# ngff-breakout.net
KiCad netlist of a schematic drawn in EAGLE
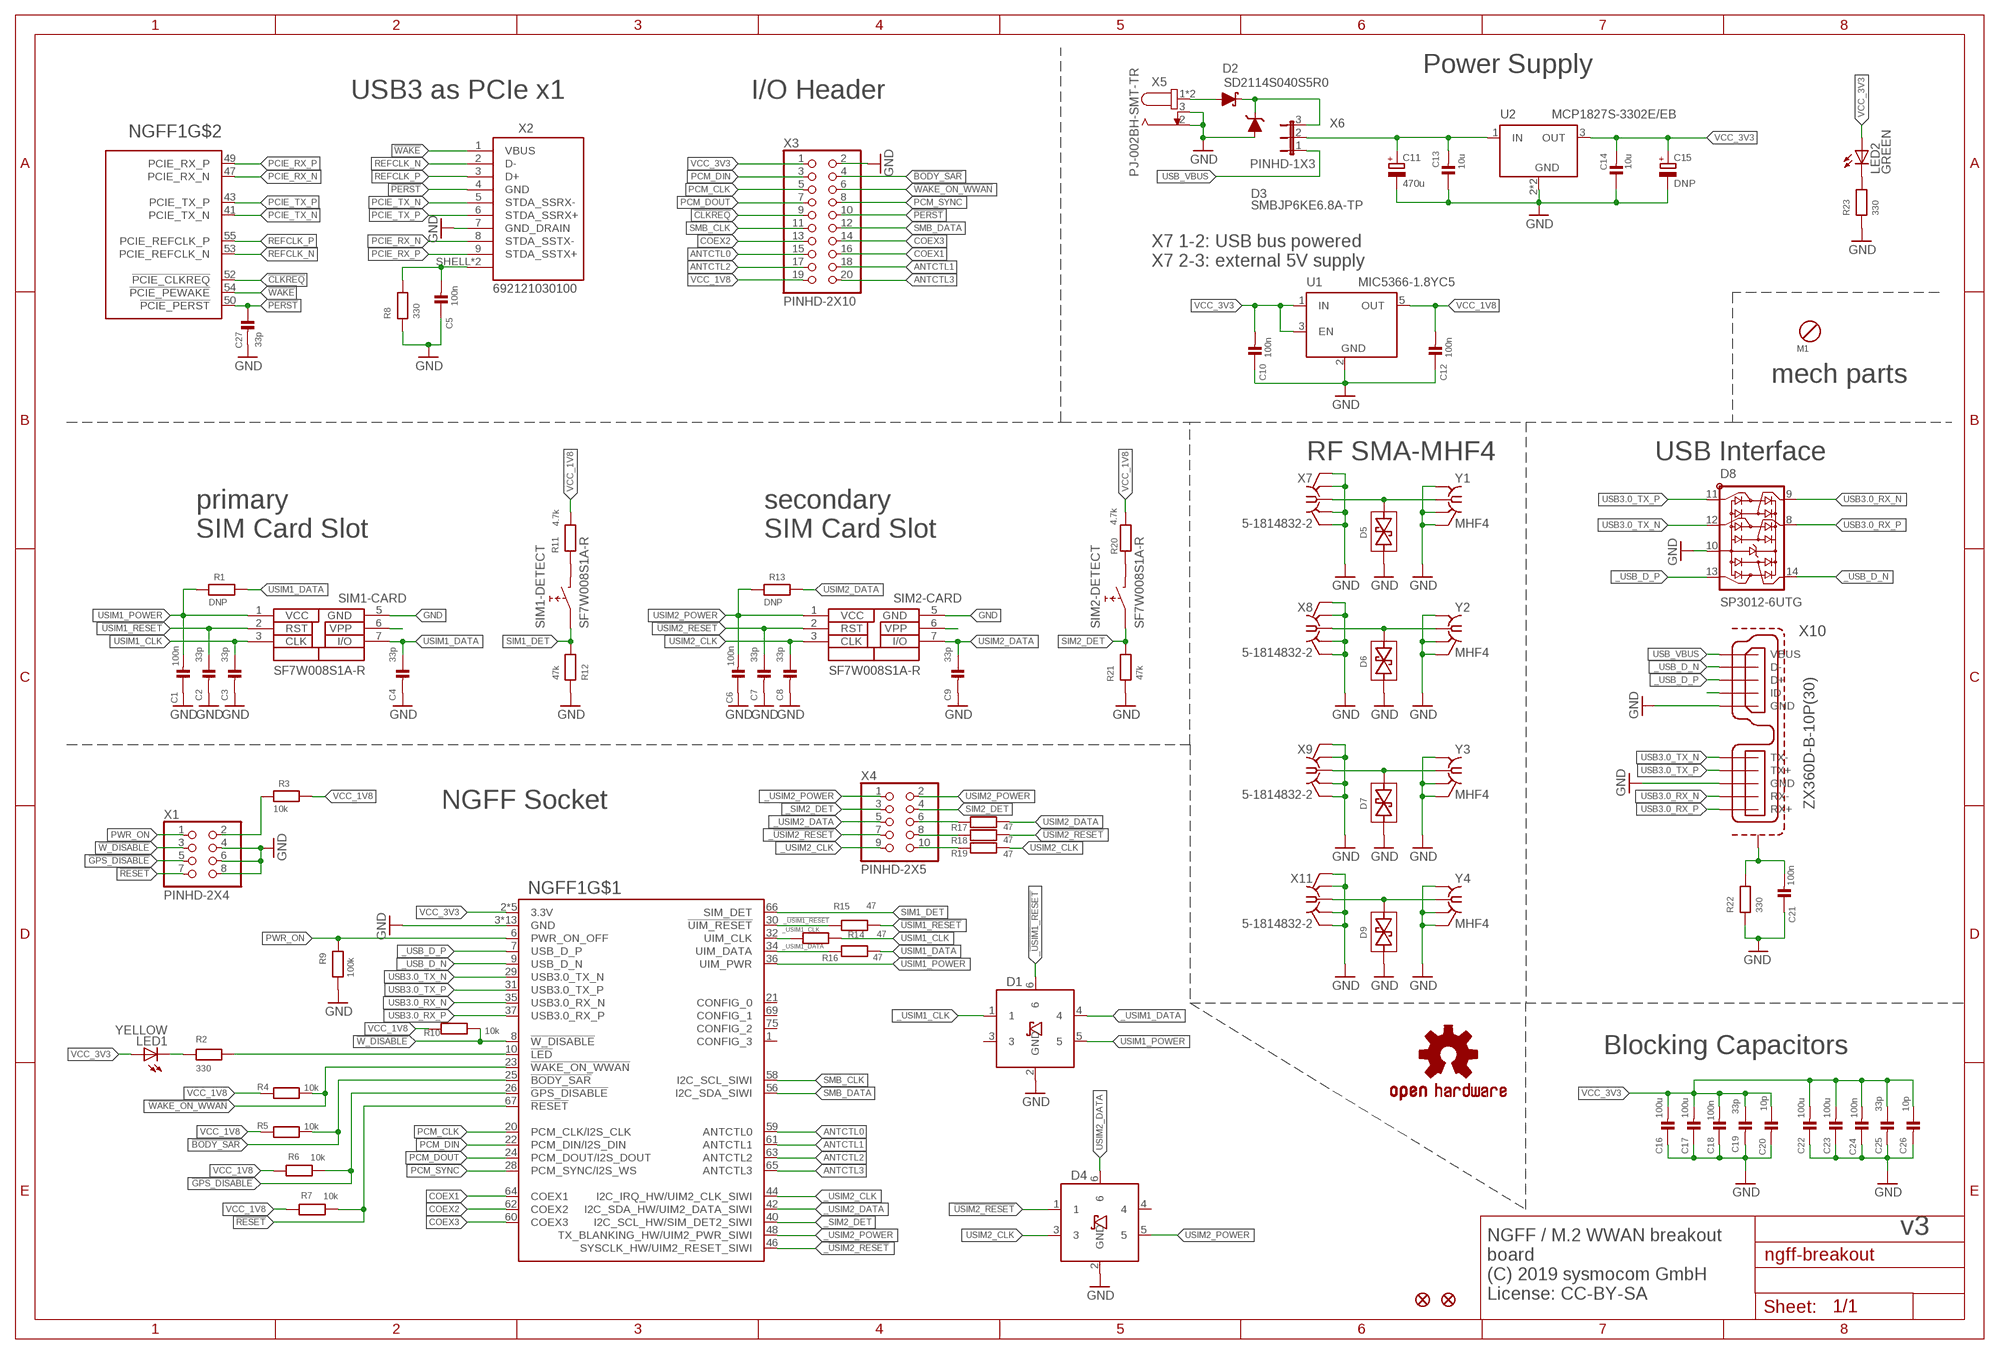
[diagram p0: schematic, sheet 1]

(export (version "E")
  (design (tool "Eeschema 10.0.6"))
  (components
    (comp (ref "C1")
      (value "100n")
      (footprint "eagle-import:_0603")
      (description "CAP CER 0.1UF 16V 10% X7R 0603")
      (fields
        (field (name "MANUFACTURER") "Samsung Electro-Mechanics America, Inc")
        (field (name "MANUFACTURERPARTNUMBER") "CL10B104KO8NNNC")
      )
      (libsource (lib "eagle-import") (part "CAP_CERAMIC_0603"))
    )
    (comp (ref "C2")
      (value "33p")
      (footprint "eagle-import:_0402")
      (description "CAP CER 33PF 50V NP0 0402")
      (fields
        (field (name "MANUFACTURER") "Samsung Electro-Mechanics America, Inc.")
        (field (name "MANUFACTURERPARTNUMBER") "CL05C330JB5NNNC")
      )
      (libsource (lib "eagle-import") (part "CAP_CERAMIC_0402"))
    )
    (comp (ref "C3")
      (value "33p")
      (footprint "eagle-import:_0402")
      (description "CAP CER 33PF 50V NP0 0402")
      (fields
        (field (name "MANUFACTURER") "Samsung Electro-Mechanics America, Inc.")
        (field (name "MANUFACTURERPARTNUMBER") "CL05C330JB5NNNC")
      )
      (libsource (lib "eagle-import") (part "CAP_CERAMIC_0402"))
    )
    (comp (ref "C4")
      (value "33p")
      (footprint "eagle-import:_0402")
      (description "CAP CER 33PF 50V NP0 0402")
      (fields
        (field (name "MANUFACTURER") "Samsung Electro-Mechanics America, Inc.")
        (field (name "MANUFACTURERPARTNUMBER") "CL05C330JB5NNNC")
      )
      (libsource (lib "eagle-import") (part "CAP_CERAMIC_0402"))
    )
    (comp (ref "C5")
      (value "100n")
      (footprint "eagle-import:_0603")
      (description "CAP CER 0.1UF 16V 10% X7R 0603")
      (fields
        (field (name "MANUFACTURER") "Samsung Electro-Mechanics America, Inc")
        (field (name "MANUFACTURERPARTNUMBER") "CL10B104KO8NNNC")
      )
      (libsource (lib "eagle-import") (part "CAP_CERAMIC_0603"))
    )
    (comp (ref "C6")
      (value "100n")
      (footprint "eagle-import:_0603")
      (description "CAP CER 0.1UF 16V 10% X7R 0603")
      (fields
        (field (name "MANUFACTURER") "Samsung Electro-Mechanics America, Inc")
        (field (name "MANUFACTURERPARTNUMBER") "CL10B104KO8NNNC")
      )
      (libsource (lib "eagle-import") (part "CAP_CERAMIC_0603"))
    )
    (comp (ref "C7")
      (value "33p")
      (footprint "eagle-import:_0402")
      (description "CAP CER 33PF 50V NP0 0402")
      (fields
        (field (name "MANUFACTURER") "Samsung Electro-Mechanics America, Inc.")
        (field (name "MANUFACTURERPARTNUMBER") "CL05C330JB5NNNC")
      )
      (libsource (lib "eagle-import") (part "CAP_CERAMIC_0402"))
    )
    (comp (ref "C8")
      (value "33p")
      (footprint "eagle-import:_0402")
      (description "CAP CER 33PF 50V NP0 0402")
      (fields
        (field (name "MANUFACTURER") "Samsung Electro-Mechanics America, Inc.")
        (field (name "MANUFACTURERPARTNUMBER") "CL05C330JB5NNNC")
      )
      (libsource (lib "eagle-import") (part "CAP_CERAMIC_0402"))
    )
    (comp (ref "C9")
      (value "33p")
      (footprint "eagle-import:_0402")
      (description "CAP CER 33PF 50V NP0 0402")
      (fields
        (field (name "MANUFACTURER") "Samsung Electro-Mechanics America, Inc.")
        (field (name "MANUFACTURERPARTNUMBER") "CL05C330JB5NNNC")
      )
      (libsource (lib "eagle-import") (part "CAP_CERAMIC_0402"))
    )
    (comp (ref "C10")
      (value "100n")
      (footprint "eagle-import:_0603")
      (description "CAP CER 0.1UF 16V 10% X7R 0603")
      (fields
        (field (name "MANUFACTURER") "Samsung Electro-Mechanics America, Inc")
        (field (name "MANUFACTURERPARTNUMBER") "CL10B104KO8NNNC")
      )
      (libsource (lib "eagle-import") (part "CAP_CERAMIC_0603"))
    )
    (comp (ref "C11")
      (value "470u")
      (footprint "eagle-import:UD-8X10_NICHICON")
      (description "CAP ALUM 470UF 20%% 6.3V SMD")
      (fields
        (field (name "MANUFACTURER") "Nichicon")
        (field (name "MANUFACTURERPARTNUMBER") "UUR0J471MNL1GS")
      )
      (libsource (lib "eagle-import") (part "CPOL-EUUD-8X10"))
    )
    (comp (ref "C12")
      (value "100n")
      (footprint "eagle-import:_0603")
      (description "CAP CER 0.1UF 16V 10% X7R 0603")
      (fields
        (field (name "MANUFACTURER") "Samsung Electro-Mechanics America, Inc")
        (field (name "MANUFACTURERPARTNUMBER") "CL10B104KO8NNNC")
      )
      (libsource (lib "eagle-import") (part "CAP_CERAMIC_0603"))
    )
    (comp (ref "C13")
      (value "10u")
      (footprint "eagle-import:_0805")
      (description "CAP CER 10UF 16V X5R 0805")
      (fields
        (field (name "MANUFACTURER") "Samsung Electro-Mechanics")
        (field (name "MANUFACTURERPARTNUMBER") "CL21A106KOQNNNG")
      )
      (libsource (lib "eagle-import") (part "CAP_CERAMIC_0805"))
    )
    (comp (ref "C14")
      (value "10u")
      (footprint "eagle-import:_0805")
      (description "CAP CER 10UF 16V X5R 0805")
      (fields
        (field (name "MANUFACTURER") "Samsung Electro-Mechanics")
        (field (name "MANUFACTURERPARTNUMBER") "CL21A106KOQNNNG")
      )
      (libsource (lib "eagle-import") (part "CAP_CERAMIC_0805"))
    )
    (comp (ref "C15")
      (value "DNP")
      (footprint "eagle-import:SMC_E")
      (description "NO DESCRIPTION")
      (fields
        (field (name "MANUFACTURER") "UNKNOWN MANUFACTURER")
        (field (name "MANUFACTURERPARTNUMBER") "UNKNOWN MANUFACTURER PART NUMBER")
      )
      (libsource (lib "eagle-import") (part "CPOL-EUSMCE"))
    )
    (comp (ref "C16")
      (value "100u")
      (footprint "eagle-import:1206")
      (description "CAP CER 100UF 6.3V X5R 1206")
      (fields
        (field (name "MANUFACTURER") "Murata Electronics North America")
        (field (name "MANUFACTURERPARTNUMBER") "GRM31CR60J107ME39K")
      )
      (libsource (lib "eagle-import") (part "CAP_CERAMIC1206"))
    )
    (comp (ref "C17")
      (value "100u")
      (footprint "eagle-import:1206")
      (description "CAP CER 100UF 6.3V X5R 1206")
      (fields
        (field (name "MANUFACTURER") "Murata Electronics North America")
        (field (name "MANUFACTURERPARTNUMBER") "GRM31CR60J107ME39K")
      )
      (libsource (lib "eagle-import") (part "CAP_CERAMIC1206"))
    )
    (comp (ref "C18")
      (value "100n")
      (footprint "eagle-import:_0603")
      (description "CAP CER 0.1UF 16V 10% X7R 0603")
      (fields
        (field (name "MANUFACTURER") "Samsung Electro-Mechanics America, Inc")
        (field (name "MANUFACTURERPARTNUMBER") "CL10B104KO8NNNC")
      )
      (libsource (lib "eagle-import") (part "CAP_CERAMIC_0603"))
    )
    (comp (ref "C19")
      (value "33p")
      (footprint "eagle-import:_0402")
      (description "CAP CER 33PF 50V NP0 0402")
      (fields
        (field (name "MANUFACTURER") "Samsung Electro-Mechanics America, Inc.")
        (field (name "MANUFACTURERPARTNUMBER") "CL05C330JB5NNNC")
      )
      (libsource (lib "eagle-import") (part "CAP_CERAMIC_0402"))
    )
    (comp (ref "C20")
      (value "10p")
      (footprint "eagle-import:_0603")
      (description "CAP CER 10PF 50V NP0 0603")
      (fields
        (field (name "MANUFACTURER") "Kemet")
        (field (name "MANUFACTURERPARTNUMBER") "C0603C100J5GACTU")
      )
      (libsource (lib "eagle-import") (part "CAP_CERAMIC_0603"))
    )
    (comp (ref "C21")
      (value "100n")
      (footprint "eagle-import:_0603")
      (description "CAP CER 0.1UF 16V 10% X7R 0603")
      (fields
        (field (name "MANUFACTURER") "Samsung Electro-Mechanics America, Inc")
        (field (name "MANUFACTURERPARTNUMBER") "CL10B104KO8NNNC")
      )
      (libsource (lib "eagle-import") (part "CAP_CERAMIC_0603"))
    )
    (comp (ref "C22")
      (value "100u")
      (footprint "eagle-import:1206")
      (description "CAP CER 100UF 6.3V X5R 1206")
      (fields
        (field (name "MANUFACTURER") "Murata Electronics North America")
        (field (name "MANUFACTURERPARTNUMBER") "GRM31CR60J107ME39K")
      )
      (libsource (lib "eagle-import") (part "CAP_CERAMIC1206"))
    )
    (comp (ref "C23")
      (value "100u")
      (footprint "eagle-import:1206")
      (description "CAP CER 100UF 6.3V X5R 1206")
      (fields
        (field (name "MANUFACTURER") "Murata Electronics North America")
        (field (name "MANUFACTURERPARTNUMBER") "GRM31CR60J107ME39K")
      )
      (libsource (lib "eagle-import") (part "CAP_CERAMIC1206"))
    )
    (comp (ref "C24")
      (value "100n")
      (footprint "eagle-import:_0603")
      (description "CAP CER 0.1UF 16V 10% X7R 0603")
      (fields
        (field (name "MANUFACTURER") "Samsung Electro-Mechanics America, Inc")
        (field (name "MANUFACTURERPARTNUMBER") "CL10B104KO8NNNC")
      )
      (libsource (lib "eagle-import") (part "CAP_CERAMIC_0603"))
    )
    (comp (ref "C25")
      (value "33p")
      (footprint "eagle-import:_0402")
      (description "CAP CER 33PF 50V NP0 0402")
      (fields
        (field (name "MANUFACTURER") "Samsung Electro-Mechanics America, Inc.")
        (field (name "MANUFACTURERPARTNUMBER") "CL05C330JB5NNNC")
      )
      (libsource (lib "eagle-import") (part "CAP_CERAMIC_0402"))
    )
    (comp (ref "C26")
      (value "10p")
      (footprint "eagle-import:_0603")
      (description "CAP CER 10PF 50V NP0 0603")
      (fields
        (field (name "MANUFACTURER") "Kemet")
        (field (name "MANUFACTURERPARTNUMBER") "C0603C100J5GACTU")
      )
      (libsource (lib "eagle-import") (part "CAP_CERAMIC_0603"))
    )
    (comp (ref "C27")
      (value "33p")
      (footprint "eagle-import:_0402")
      (description "CAP CER 33PF 50V NP0 0402")
      (fields
        (field (name "MANUFACTURER") "Samsung Electro-Mechanics America, Inc.")
        (field (name "MANUFACTURERPARTNUMBER") "CL05C330JB5NNNC")
      )
      (libsource (lib "eagle-import") (part "CAP_CERAMIC_0402"))
    )
    (comp (ref "D1")
      (value "PESD5V0UBV")
      (footprint "eagle-import:SOT666")
      (description "TVS DIODE 5V SOT666")
      (fields
        (field (name "MANUFACTURER") "Nexperia USA Inc.")
        (field (name "MANUFACTURERPARTNUMBER") "PESD5V0U5BV,115")
      )
      (libsource (lib "eagle-import") (part "PESD5V0UBV"))
    )
    (comp (ref "D2")
      (value "SD2114S040S5R0")
      (footprint "eagle-import:SMBDIODE")
      (description "DIODE SCHOTTKY 40V 5A SMB")
      (fields
        (field (name "MANUFACTURER") "AVX Corporation")
        (field (name "MANUFACTURERPARTNUMBER") "YPE HTML PUBLIC ")
      )
      (libsource (lib "eagle-import") (part "DIODE-SCHOTTKY-SMB"))
    )
    (comp (ref "D3")
      (value "SMBJP6KE6.8A-TP")
      (footprint "eagle-import:SMBDIODE")
      (description "TVS DIODE 5.8V 10.5V DO214AA")
      (fields (field (name "MANUFACTURER") "Micro Commercial Co"))
      (libsource (lib "eagle-import") (part "DIODE-TVS-SMB"))
    )
    (comp (ref "D4")
      (value "PESD5V0UBV")
      (footprint "eagle-import:SOT666")
      (description "TVS DIODE 5V SOT666")
      (fields
        (field (name "MANUFACTURER") "Nexperia USA Inc.")
        (field (name "MANUFACTURERPARTNUMBER") "PESD5V0U5BV,115")
      )
      (libsource (lib "eagle-import") (part "PESD5V0UBV"))
    )
    (comp (ref "D5")
      (value "GG040205170N2P")
      (footprint "eagle-import:_0402")
      (description "TVS DIODE 5V 10V 0402")
      (fields (field (name "MANUFACTURER") "AVX Corporation"))
      (libsource (lib "eagle-import") (part "TVSDIODE-BIDI-0402"))
    )
    (comp (ref "D6")
      (value "GG040205170N2P")
      (footprint "eagle-import:_0402")
      (description "TVS DIODE 5V 10V 0402")
      (fields (field (name "MANUFACTURER") "AVX Corporation"))
      (libsource (lib "eagle-import") (part "TVSDIODE-BIDI-0402"))
    )
    (comp (ref "D7")
      (value "GG040205170N2P")
      (footprint "eagle-import:_0402")
      (description "TVS DIODE 5V 10V 0402")
      (fields (field (name "MANUFACTURER") "AVX Corporation"))
      (libsource (lib "eagle-import") (part "TVSDIODE-BIDI-0402"))
    )
    (comp (ref "D8")
      (value "SP3012-6UTG")
      (footprint "eagle-import:UDFN-14")
      (description "TVS DIODE 5V 7V 14UDFN")
      (fields
        (field (name "MANUFACTURER") "Littelfuse Inc.")
        (field (name "MANUFACTURERPARTNUMBER") "SP3012-06UTG")
      )
      (libsource (lib "eagle-import") (part "SP3012-6UTG"))
    )
    (comp (ref "D9")
      (value "GG040205170N2P")
      (footprint "eagle-import:_0402")
      (description "TVS DIODE 5V 10V 0402")
      (fields (field (name "MANUFACTURER") "AVX Corporation"))
      (libsource (lib "eagle-import") (part "TVSDIODE-BIDI-0402"))
    )
    (comp (ref "JP1")
      (value "FIDUCIALUFIDUCIAL")
      (footprint "eagle-import:MICRO-FIDUCIAL")
      (description "NO DESCRIPTION")
      (fields
        (field (name "MANUFACTURER") "UNKNOWN MANUFACTURER")
        (field (name "MANUFACTURERPARTNUMBER") "UNKNOWN MANUFACTURER PART NUMBER")
      )
      (libsource (lib "eagle-import") (part "FIDUCIALUFIDUCIAL"))
    )
    (comp (ref "JP2")
      (value "FIDUCIALUFIDUCIAL")
      (footprint "eagle-import:MICRO-FIDUCIAL")
      (description "NO DESCRIPTION")
      (fields
        (field (name "MANUFACTURER") "UNKNOWN MANUFACTURER")
        (field (name "MANUFACTURERPARTNUMBER") "UNKNOWN MANUFACTURER PART NUMBER")
      )
      (libsource (lib "eagle-import") (part "FIDUCIALUFIDUCIAL"))
    )
    (comp (ref "LED1")
      (value "YELLOW")
      (footprint "eagle-import:CHIP-LED0603")
      (description "NO DESCRIPTION")
      (fields
        (field (name "MANUFACTURER") "UNKNOWN MANUFACTURER")
        (field (name "MANUFACTURERPARTNUMBER") "UNKNOWN MANUFACTURER PART NUMBER")
      )
      (libsource (lib "eagle-import") (part "LEDCHIP-LED0603"))
    )
    (comp (ref "LED2")
      (value "GREEN")
      (footprint "eagle-import:CHIP-LED0603")
      (description "NO DESCRIPTION")
      (fields
        (field (name "MANUFACTURER") "UNKNOWN MANUFACTURER")
        (field (name "MANUFACTURERPARTNUMBER") "UNKNOWN MANUFACTURER PART NUMBER")
      )
      (libsource (lib "eagle-import") (part "LEDCHIP-LED0603"))
    )
    (comp (ref "LOGO1")
      (value "OSHW-LOGOL-COPPER")
      (footprint "eagle-import:OSHW-LOGO-L_COPPER")
      (description "NO DESCRIPTION")
      (fields
        (field (name "MANUFACTURER") "UNKNOWN MANUFACTURER")
        (field (name "MANUFACTURERPARTNUMBER") "UNKNOWN MANUFACTURER PART NUMBER")
      )
      (libsource (lib "eagle-import") (part "OSHW-LOGOL-COPPER"))
    )
    (comp (ref "NGFF1")
      (value "NGFF_B-NSOL")
      (footprint "eagle-import:NGFF_3042_3052_NSOL")
      (description "CONN FEMALE 67POS 0.020 GOLD")
      (fields
        (field (name "CLASS") "CONNECTOR")
        (field (name "LINK") "https://www.digikey.de/product-detail/de/te-connectivity-amp-connectors/2199230-3/A115903CT-ND")
        (field (name "MANUFACTURER") "TE Connectivity AMP Connectors")
        (field (name "MANUFACTURERPARTNUMBER") "2199230-3")
        (field (name "POPULATED") "TRUE")
        (field (name "ROHSCERTIFICATE") "RoHS-konform")
        (field (name "SOURCE") "DIGIKEY")
        (field (name "SOURCEPARTNUMBER") "A115903CT-ND")
      )
      (libsource (lib "eagle-import") (part "NGFF_B-NSOL"))
    )
    (comp (ref "R1")
      (value "DNP")
      (footprint "eagle-import:_0603")
      (description "RES 10K OHM 1%% 1/10W 0603")
      (fields
        (field (name "MANUFACTURER") "Stackpole Electronics Inc")
        (field (name "MANUFACTURERPARTNUMBER") "YPE HTML PUBLIC ")
      )
      (libsource (lib "eagle-import") (part "RESISTOR_0603"))
    )
    (comp (ref "R2")
      (value "330")
      (footprint "eagle-import:_0603")
      (description "RES SMD 330 OHM 5%% 1/10W 0603")
      (fields
        (field (name "MANUFACTURER") "Yageo")
        (field (name "MANUFACTURERPARTNUMBER") "RC0603JR-07330RL")
      )
      (libsource (lib "eagle-import") (part "RESISTOR_0603"))
    )
    (comp (ref "R3")
      (value "10k")
      (footprint "eagle-import:_0603")
      (description "RES 10K OHM 1%% 1/10W 0603")
      (fields
        (field (name "MANUFACTURER") "Stackpole Electronics Inc")
        (field (name "MANUFACTURERPARTNUMBER") "YPE HTML PUBLIC ")
      )
      (libsource (lib "eagle-import") (part "RESISTOR_0603"))
    )
    (comp (ref "R4")
      (value "10k")
      (footprint "eagle-import:_0603")
      (description "RES 10K OHM 1%% 1/10W 0603")
      (fields
        (field (name "MANUFACTURER") "Stackpole Electronics Inc")
        (field (name "MANUFACTURERPARTNUMBER") "YPE HTML PUBLIC ")
      )
      (libsource (lib "eagle-import") (part "RESISTOR_0603"))
    )
    (comp (ref "R5")
      (value "10k")
      (footprint "eagle-import:_0603")
      (description "RES 10K OHM 1%% 1/10W 0603")
      (fields
        (field (name "MANUFACTURER") "Stackpole Electronics Inc")
        (field (name "MANUFACTURERPARTNUMBER") "YPE HTML PUBLIC ")
      )
      (libsource (lib "eagle-import") (part "RESISTOR_0603"))
    )
    (comp (ref "R6")
      (value "10k")
      (footprint "eagle-import:_0603")
      (description "RES 10K OHM 1%% 1/10W 0603")
      (fields
        (field (name "MANUFACTURER") "Stackpole Electronics Inc")
        (field (name "MANUFACTURERPARTNUMBER") "RMCF0603FT10K0")
      )
      (libsource (lib "eagle-import") (part "RESISTOR_0603"))
    )
    (comp (ref "R7")
      (value "10k")
      (footprint "eagle-import:_0603")
      (description "RES 10K OHM 1%% 1/10W 0603")
      (fields
        (field (name "MANUFACTURER") "Stackpole Electronics Inc")
        (field (name "MANUFACTURERPARTNUMBER") "YPE HTML PUBLIC ")
      )
      (libsource (lib "eagle-import") (part "RESISTOR_0603"))
    )
    (comp (ref "R8")
      (value "330")
      (footprint "eagle-import:_0603")
      (description "RES SMD 330 OHM 5%% 1/10W 0603")
      (fields
        (field (name "MANUFACTURER") "Yageo")
        (field (name "MANUFACTURERPARTNUMBER") "RC0603JR-07330RL")
      )
      (libsource (lib "eagle-import") (part "RESISTOR_0603"))
    )
    (comp (ref "R9")
      (value "100k")
      (footprint "eagle-import:_0603")
      (description "RES SMD 100K OHM 1%% 1/10W 0603")
      (fields
        (field (name "MANUFACTURER") "Vishay Dale")
        (field (name "MANUFACTURERPARTNUMBER") "CRCW0603100KFKEA")
      )
      (libsource (lib "eagle-import") (part "RESISTOR_0603"))
    )
    (comp (ref "R10")
      (value "10k")
      (footprint "eagle-import:_0603")
      (description "RES 10K OHM 1%% 1/10W 0603")
      (fields
        (field (name "MANUFACTURER") "Stackpole Electronics Inc")
        (field (name "MANUFACTURERPARTNUMBER") "YPE HTML PUBLIC ")
      )
      (libsource (lib "eagle-import") (part "RESISTOR_0603"))
    )
    (comp (ref "R11")
      (value "4.7k")
      (footprint "eagle-import:_0603")
      (description "RES SMD 4.7K OHM 5% 1/10W 0603")
      (fields (field (name "MANUFACTURER") "Yageo") (field (name "MANUFACTURERPARTNUMBER") "RC0603JR-074K7L"))
      (libsource (lib "eagle-import") (part "RESISTOR_0603"))
    )
    (comp (ref "R12")
      (value "47k")
      (footprint "eagle-import:_0603")
      (description "RES 47K OHM 1%% 1/10W 0603")
      (fields
        (field (name "MANUFACTURER") "Stackpole Electronics Inc")
        (field (name "MANUFACTURERPARTNUMBER") "RMCF0603FT47K0")
      )
      (libsource (lib "eagle-import") (part "RESISTOR_0603"))
    )
    (comp (ref "R13")
      (value "DNP")
      (footprint "eagle-import:_0603")
      (description "RES 10K OHM 1%% 1/10W 0603")
      (fields
        (field (name "MANUFACTURER") "Stackpole Electronics Inc")
        (field (name "MANUFACTURERPARTNUMBER") "YPE HTML PUBLIC ")
      )
      (libsource (lib "eagle-import") (part "RESISTOR_0603"))
    )
    (comp (ref "R14")
      (value "47")
      (footprint "eagle-import:_0402")
      (description "RES SMD 47R 0402 1%")
      (fields
        (field (name "MANUFACTURER") "TE Connectivity Passive Product")
        (field (name "MANUFACTURERPARTNUMBER") "CRGCQ0402F47R")
      )
      (libsource (lib "eagle-import") (part "RESISTOR_0402"))
    )
    (comp (ref "R15")
      (value "47")
      (footprint "eagle-import:_0402")
      (description "RES SMD 47R 0402 1%")
      (fields
        (field (name "MANUFACTURER") "TE Connectivity Passive Product")
        (field (name "MANUFACTURERPARTNUMBER") "CRGCQ0402F47R")
      )
      (libsource (lib "eagle-import") (part "RESISTOR_0402"))
    )
    (comp (ref "R16")
      (value "47")
      (footprint "eagle-import:_0402")
      (description "RES SMD 47R 0402 1%")
      (fields
        (field (name "MANUFACTURER") "TE Connectivity Passive Product")
        (field (name "MANUFACTURERPARTNUMBER") "CRGCQ0402F47R")
      )
      (libsource (lib "eagle-import") (part "RESISTOR_0402"))
    )
    (comp (ref "R17")
      (value "47")
      (footprint "eagle-import:_0402")
      (description "RES SMD 47R 0402 1%")
      (fields
        (field (name "MANUFACTURER") "TE Connectivity Passive Product")
        (field (name "MANUFACTURERPARTNUMBER") "CRGCQ0402F47R")
      )
      (libsource (lib "eagle-import") (part "RESISTOR_0402"))
    )
    (comp (ref "R18")
      (value "47")
      (footprint "eagle-import:_0402")
      (description "RES SMD 47R 0402 1%")
      (fields
        (field (name "MANUFACTURER") "TE Connectivity Passive Product")
        (field (name "MANUFACTURERPARTNUMBER") "CRGCQ0402F47R")
      )
      (libsource (lib "eagle-import") (part "RESISTOR_0402"))
    )
    (comp (ref "R19")
      (value "47")
      (footprint "eagle-import:_0402")
      (description "RES SMD 47R 0402 1%")
      (fields
        (field (name "MANUFACTURER") "TE Connectivity Passive Product")
        (field (name "MANUFACTURERPARTNUMBER") "CRGCQ0402F47R")
      )
      (libsource (lib "eagle-import") (part "RESISTOR_0402"))
    )
    (comp (ref "R20")
      (value "4.7k")
      (footprint "eagle-import:_0603")
      (description "RES SMD 4.7K OHM 5% 1/10W 0603")
      (fields (field (name "MANUFACTURER") "Yageo") (field (name "MANUFACTURERPARTNUMBER") "RC0603JR-074K7L"))
      (libsource (lib "eagle-import") (part "RESISTOR_0603"))
    )
    (comp (ref "R21")
      (value "47k")
      (footprint "eagle-import:_0603")
      (description "RES 47K OHM 1%% 1/10W 0603")
      (fields
        (field (name "MANUFACTURER") "Stackpole Electronics Inc")
        (field (name "MANUFACTURERPARTNUMBER") "RMCF0603FT47K0")
      )
      (libsource (lib "eagle-import") (part "RESISTOR_0603"))
    )
    (comp (ref "R22")
      (value "330")
      (footprint "eagle-import:_0603")
      (description "RES SMD 330 OHM 5%% 1/10W 0603")
      (fields
        (field (name "MANUFACTURER") "Yageo")
        (field (name "MANUFACTURERPARTNUMBER") "RC0603JR-07330RL")
      )
      (libsource (lib "eagle-import") (part "RESISTOR_0603"))
    )
    (comp (ref "R23")
      (value "330")
      (footprint "eagle-import:_0603")
      (description "RES SMD 330 OHM 5%% 1/10W 0603")
      (fields
        (field (name "MANUFACTURER") "Yageo")
        (field (name "MANUFACTURERPARTNUMBER") "RC0603JR-07330RL")
      )
      (libsource (lib "eagle-import") (part "RESISTOR_0603"))
    )
    (comp (ref "SIM1")
      (value "SF7W008S1A-R")
      (footprint "eagle-import:SF7W008S1A-RESTR")
      (description "CONN SIM CARD HINGED TYPE R/A")
      (fields
        (field (name "MANUFACTURER") "JAE Electronics")
        (field (name "MANUFACTURERPARTNUMBER") "SF7W008S1AR900")
        (field (name "CLASS") "SIM CARD HOLDER")
        (field (name "LINK") "https://www.digikey.de/product-detail/de/jae-electronics/SF7W008S1AR900/670-2985-1-ND")
        (field (name "POPULATED") "TRUE")
        (field (name "ROHSCERTIFICATE") "RoHS-konform")
        (field (name "SOURCE") "DIGIKEY")
        (field (name "SOURCEPARTNUMBER") "670-2985-1-ND")
      )
      (libsource (lib "eagle-import") (part "SF7W008S1A-R"))
    )
    (comp (ref "SIM2")
      (value "SF7W008S1A-R")
      (footprint "eagle-import:SF7W008S1A-RESTR")
      (description "CONN SIM CARD HINGED TYPE R/A")
      (fields
        (field (name "CLASS") "SIM CARD HOLDER")
        (field (name "LINK") "https://www.digikey.de/product-detail/de/jae-electronics/SF7W008S1AR900/670-2985-1-ND")
        (field (name "MANUFACTURER") "JAE Electronics")
        (field (name "MANUFACTURERPARTNUMBER") "SF7W008S1AR900")
        (field (name "POPULATED") "TRUE")
        (field (name "ROHSCERTIFICATE") "RoHS-konform")
        (field (name "SOURCE") "DIGIKEY")
        (field (name "SOURCEPARTNUMBER") "670-2985-1-ND")
      )
      (libsource (lib "eagle-import") (part "SF7W008S1A-R"))
    )
    (comp (ref "U1")
      (value "MIC5366-1.8YC5")
      (footprint "eagle-import:SC70-5")
      (description "IC REG LINEAR 1.8V 150MA SC70-5")
      (fields
        (field (name "MANUFACTURER") "Microchip Technology")
        (field (name "MANUFACTURERPARTNUMBER") "MIC5366-1.8YC5-TR")
      )
      (libsource (lib "eagle-import") (part "LDO_FIXED_EN-MIC5365-YC5"))
    )
    (comp (ref "U2")
      (value "MCP1827S-3302E/EB")
      (footprint "eagle-import:TO263")
      (description "IC REG LINEAR 3.3V 1.5A 3DDPAK")
      (fields
        (field (name "MANUFACTURER") "Microchip Technology")
        (field (name "MANUFACTURERPARTNUMBER") "YPE HTML PUBLIC ")
      )
      (libsource (lib "eagle-import") (part "LDO-MCP1827S"))
    )
    (comp (ref "X1")
      (value "PINHD-2X4")
      (footprint "eagle-import:2X04")
      (description "CONN HEADER VERT 8POS 2.54MM")
      (fields (field (name "MANUFACTURER") "Adam Tech") (field (name "MANUFACTURERPARTNUMBER") "PH2-08-UA"))
      (libsource (lib "eagle-import") (part "PINHD-2X4"))
    )
    (comp (ref "X2")
      (value "692121030100")
      (footprint "eagle-import:692121030100")
      (description "CONN RCPT USB3.0 TYPEA 9POS R/A")
      (fields (field (name "MANUFACTURER") "W&#252;rth Elektronik"))
      (libsource (lib "eagle-import") (part "692121030100"))
    )
    (comp (ref "X3")
      (value "PINHD-2X10")
      (footprint "eagle-import:2X10")
      (description "CONN HEADER VERT 20POS 2.54MM")
      (fields (field (name "MANUFACTURER") "Adam Tech") (field (name "MANUFACTURERPARTNUMBER") "PH2-20-UA"))
      (libsource (lib "eagle-import") (part "PINHD-2X10"))
    )
    (comp (ref "X4")
      (value "PINHD-2X5")
      (footprint "eagle-import:2X05")
      (description "CONN HEADER VERT 10POS 2.54MM")
      (fields (field (name "MANUFACTURER") "Adam Tech") (field (name "MANUFACTURERPARTNUMBER") "PH2-10-UA"))
      (libsource (lib "eagle-import") (part "PINHD-2X5"))
    )
    (comp (ref "X5")
      (value "PJ-002BH-SMT-TR")
      (footprint "eagle-import:694108106102")
      (description "CONN PWR JACK 2.5X5.5MM SOLDER")
      (fields (field (name "MANUFACTURER") "CUI Devices"))
      (libsource (lib "eagle-import") (part "694108106102"))
    )
    (comp (ref "X6")
      (value "PINHD-1X3")
      (footprint "eagle-import:JP2")
      (description "CONN HEADER VERT 3POS 2.54MM")
      (fields (field (name "MANUFACTURER") "Adam Tech") (field (name "MANUFACTURERPARTNUMBER") "PH1-03-UA"))
      (libsource (lib "eagle-import") (part "JP2E"))
    )
    (comp (ref "X7")
      (value "5-1814832-2")
      (footprint "eagle-import:SMA-F-S-TH")
      (description "SMA STR PCB SKT GZD")
      (fields (field (name "MANUFACTURER") "TE Connectivity AMP Connectors"))
      (libsource (lib "eagle-import") (part "SMA-F-S-TH"))
    )
    (comp (ref "X8")
      (value "5-1814832-2")
      (footprint "eagle-import:SMA-F-S-TH")
      (description "SMA STR PCB SKT GZD")
      (fields (field (name "MANUFACTURER") "TE Connectivity AMP Connectors"))
      (libsource (lib "eagle-import") (part "SMA-F-S-TH"))
    )
    (comp (ref "X9")
      (value "5-1814832-2")
      (footprint "eagle-import:SMA-F-S-TH")
      (description "SMA STR PCB SKT GZD")
      (fields (field (name "MANUFACTURER") "TE Connectivity AMP Connectors"))
      (libsource (lib "eagle-import") (part "SMA-F-S-TH"))
    )
    (comp (ref "X10")
      (value "ZX360D-B-10P(30)")
      (footprint "eagle-import:ZX360D-B")
      (description "CONN RCPT USB3.0 MICRO B SMD R/A")
      (fields (field (name "MANUFACTURER") "Hirose Electric Co Ltd"))
      (libsource (lib "eagle-import") (part "USB3.0-MICROB"))
    )
    (comp (ref "X11")
      (value "5-1814832-2")
      (footprint "eagle-import:SMA-F-S-TH")
      (description "SMA STR PCB SKT GZD")
      (fields (field (name "MANUFACTURER") "TE Connectivity AMP Connectors"))
      (libsource (lib "eagle-import") (part "SMA-F-S-TH"))
    )
    (comp (ref "Y1")
      (value "MHF4")
      (footprint "eagle-import:MURATA_HSC")
      (description "CONN HSC RCPT STR 50 OHM SMD")
      (fields
        (field (name "MANUFACTURER") "Murata Electronics")
        (field (name "MANUFACTURERPARTNUMBER") "MM4829-2702RA4")
      )
      (libsource (lib "eagle-import") (part "MHF4"))
    )
    (comp (ref "Y2")
      (value "MHF4")
      (footprint "eagle-import:MURATA_HSC")
      (description "CONN HSC RCPT STR 50 OHM SMD")
      (fields
        (field (name "MANUFACTURER") "Murata Electronics")
        (field (name "MANUFACTURERPARTNUMBER") "MM4829-2702RA4")
      )
      (libsource (lib "eagle-import") (part "MHF4"))
    )
    (comp (ref "Y3")
      (value "MHF4")
      (footprint "eagle-import:MURATA_HSC")
      (description "CONN HSC RCPT STR 50 OHM SMD")
      (fields
        (field (name "MANUFACTURER") "Murata Electronics")
        (field (name "MANUFACTURERPARTNUMBER") "MM4829-2702RA4")
      )
      (libsource (lib "eagle-import") (part "MHF4"))
    )
    (comp (ref "Y4")
      (value "MHF4")
      (footprint "eagle-import:MURATA_HSC")
      (description "CONN HSC RCPT STR 50 OHM SMD")
      (fields
        (field (name "MANUFACTURER") "Murata Electronics")
        (field (name "MANUFACTURERPARTNUMBER") "MM4829-2702RA4")
      )
      (libsource (lib "eagle-import") (part "MHF4"))
    )
  )
  (nets
    (net (code "1") (name "/_~{USIM1_RESET}") (class "Default")
      (node (ref "D1") (pin "6") (pinfunction "6_6") (pintype "passive"))
      (node (ref "NGFF1") (pin "30") (pinfunction "~{UIM_RESET}_30") (pintype "output"))
      (node (ref "R15") (pin "1") (pinfunction "1_1") (pintype "passive"))
    )
    (net (code "2") (name "/_~{USIM2_RESET}") (class "Default")
      (node (ref "NGFF1") (pin "46") (pinfunction "SYSCLK_HW/UIM2_RESET_SIWI_46") (pintype "output"))
      (node (ref "X4") (pin "7") (pinfunction "7_7") (pintype "passive"))
    )
    (net (code "3") (name "/~{BODY_SAR}") (class "Default")
      (node (ref "NGFF1") (pin "25") (pinfunction "~{BODY_SAR}_25") (pintype "input"))
      (node (ref "R5") (pin "1") (pinfunction "1_1") (pintype "passive"))
      (node (ref "X3") (pin "4") (pinfunction "4_4") (pintype "passive"))
    )
    (net (code "4") (name "/~{CLKREQ}") (class "Default")
      (node (ref "NGFF1") (pin "52") (pinfunction "~{PCIE_CLKREQ}_52") (pintype "open_collector"))
      (node (ref "X3") (pin "9") (pinfunction "9_9") (pintype "passive"))
    )
    (net (code "5") (name "/~{GPS_DISABLE}") (class "Default")
      (node (ref "NGFF1") (pin "26") (pinfunction "~{GPS_DISABLE}_26") (pintype "input"))
      (node (ref "R6") (pin "1") (pinfunction "1_1") (pintype "passive"))
      (node (ref "X1") (pin "5") (pinfunction "5_5") (pintype "passive"))
    )
    (net (code "6") (name "/~{PERST}") (class "Default")
      (node (ref "C27") (pin "1") (pinfunction "1_1") (pintype "passive"))
      (node (ref "NGFF1") (pin "50") (pinfunction "~{PCIE_PERST}_50") (pintype "input"))
      (node (ref "X2") (pin "4") (pinfunction "GND_4") (pintype "bidirectional"))
      (node (ref "X3") (pin "10") (pinfunction "10_10") (pintype "passive"))
    )
    (net (code "7") (name "/~{RESET}") (class "Default")
      (node (ref "NGFF1") (pin "67") (pinfunction "~{RESET}_67") (pintype "input"))
      (node (ref "R7") (pin "1") (pinfunction "1_1") (pintype "passive"))
      (node (ref "X1") (pin "7") (pinfunction "7_7") (pintype "passive"))
    )
    (net (code "8") (name "/~{USIM1_RESET}") (class "Default")
      (node (ref "C2") (pin "1") (pinfunction "1_1") (pintype "passive"))
      (node (ref "R15") (pin "2") (pinfunction "2_2") (pintype "passive"))
      (node (ref "SIM1") (pin "2") (pinfunction "RST_2") (pintype "input"))
    )
    (net (code "9") (name "/~{USIM2_RESET}") (class "Default")
      (node (ref "C7") (pin "1") (pinfunction "1_1") (pintype "passive"))
      (node (ref "D4") (pin "1") (pinfunction "1_1") (pintype "passive"))
      (node (ref "R18") (pin "2") (pinfunction "2_2") (pintype "passive"))
      (node (ref "SIM2") (pin "2") (pinfunction "RST_2") (pintype "input"))
    )
    (net (code "10") (name "/~{WAKE_ON_WWAN}") (class "Default")
      (node (ref "NGFF1") (pin "23") (pinfunction "~{WAKE_ON_WWAN}_23") (pintype "output"))
      (node (ref "R4") (pin "1") (pinfunction "1_1") (pintype "passive"))
      (node (ref "X3") (pin "6") (pinfunction "6_6") (pintype "passive"))
    )
    (net (code "11") (name "/~{WAKE}") (class "Default")
      (node (ref "NGFF1") (pin "54") (pinfunction "~{PCIE_PEWAKE}_54") (pintype "open_collector"))
      (node (ref "X2") (pin "1") (pinfunction "VBUS_1") (pintype "bidirectional"))
    )
    (net (code "12") (name "/~{W_DISABLE}") (class "Default")
      (node (ref "NGFF1") (pin "8") (pinfunction "~{W_DISABLE}_8") (pintype "input"))
      (node (ref "R10") (pin "1") (pinfunction "1_1") (pintype "passive"))
      (node (ref "X1") (pin "3") (pinfunction "3_3") (pintype "passive"))
    )
    (net (code "13") (name "ANTCTL0") (class "Default")
      (node (ref "NGFF1") (pin "59") (pinfunction "ANTCTL0_59") (pintype "output"))
      (node (ref "X3") (pin "15") (pinfunction "15_15") (pintype "passive"))
    )
    (net (code "14") (name "ANTCTL1") (class "Default")
      (node (ref "NGFF1") (pin "61") (pinfunction "ANTCTL1_61") (pintype "output"))
      (node (ref "X3") (pin "18") (pinfunction "18_18") (pintype "passive"))
    )
    (net (code "15") (name "ANTCTL2") (class "Default")
      (node (ref "NGFF1") (pin "63") (pinfunction "ANTCTL2_63") (pintype "output"))
      (node (ref "X3") (pin "17") (pinfunction "17_17") (pintype "passive"))
    )
    (net (code "16") (name "ANTCTL3") (class "Default")
      (node (ref "NGFF1") (pin "65") (pinfunction "ANTCTL3_65") (pintype "output"))
      (node (ref "X3") (pin "20") (pinfunction "20_20") (pintype "passive"))
    )
    (net (code "17") (name "COEX1") (class "Default")
      (node (ref "NGFF1") (pin "64") (pinfunction "COEX1_64") (pintype "bidirectional"))
      (node (ref "X3") (pin "16") (pinfunction "16_16") (pintype "passive"))
    )
    (net (code "18") (name "COEX2") (class "Default")
      (node (ref "NGFF1") (pin "62") (pinfunction "COEX2_62") (pintype "bidirectional"))
      (node (ref "X3") (pin "13") (pinfunction "13_13") (pintype "passive"))
    )
    (net (code "19") (name "COEX3") (class "Default")
      (node (ref "NGFF1") (pin "60") (pinfunction "COEX3_60") (pintype "bidirectional"))
      (node (ref "X3") (pin "14") (pinfunction "14_14") (pintype "passive"))
    )
    (net (code "20") (name "GND") (class "Default")
      (node (ref "C1") (pin "1") (pinfunction "1_1") (pintype "passive"))
      (node (ref "C10") (pin "1") (pinfunction "1_1") (pintype "passive"))
      (node (ref "C11") (pin "-") (pinfunction "-_-") (pintype "passive"))
      (node (ref "C12") (pin "1") (pinfunction "1_1") (pintype "passive"))
      (node (ref "C13") (pin "1") (pinfunction "1_1") (pintype "passive"))
      (node (ref "C14") (pin "1") (pinfunction "1_1") (pintype "passive"))
      (node (ref "C15") (pin "-") (pinfunction "-_-") (pintype "passive"))
      (node (ref "C16") (pin "1") (pinfunction "1_1") (pintype "passive"))
      (node (ref "C17") (pin "1") (pinfunction "1_1") (pintype "passive"))
      (node (ref "C18") (pin "1") (pinfunction "1_1") (pintype "passive"))
      (node (ref "C19") (pin "2") (pinfunction "2_2") (pintype "passive"))
      (node (ref "C2") (pin "2") (pinfunction "2_2") (pintype "passive"))
      (node (ref "C20") (pin "2") (pinfunction "2_2") (pintype "passive"))
      (node (ref "C21") (pin "1") (pinfunction "1_1") (pintype "passive"))
      (node (ref "C22") (pin "1") (pinfunction "1_1") (pintype "passive"))
      (node (ref "C23") (pin "1") (pinfunction "1_1") (pintype "passive"))
      (node (ref "C24") (pin "1") (pinfunction "1_1") (pintype "passive"))
      (node (ref "C25") (pin "2") (pinfunction "2_2") (pintype "passive"))
      (node (ref "C26") (pin "2") (pinfunction "2_2") (pintype "passive"))
      (node (ref "C27") (pin "2") (pinfunction "2_2") (pintype "passive"))
      (node (ref "C3") (pin "2") (pinfunction "2_2") (pintype "passive"))
      (node (ref "C4") (pin "2") (pinfunction "2_2") (pintype "passive"))
      (node (ref "C5") (pin "1") (pinfunction "1_1") (pintype "passive"))
      (node (ref "C6") (pin "1") (pinfunction "1_1") (pintype "passive"))
      (node (ref "C7") (pin "2") (pinfunction "2_2") (pintype "passive"))
      (node (ref "C8") (pin "2") (pinfunction "2_2") (pintype "passive"))
      (node (ref "C9") (pin "2") (pinfunction "2_2") (pintype "passive"))
      (node (ref "D1") (pin "2") (pinfunction "GND_2") (pintype "passive"))
      (node (ref "D3") (pin "A") (pinfunction "A_A") (pintype "passive"))
      (node (ref "D4") (pin "2") (pinfunction "GND_2") (pintype "passive"))
      (node (ref "D5") (pin "1") (pinfunction "P$1_1") (pintype "bidirectional"))
      (node (ref "D6") (pin "1") (pinfunction "P$1_1") (pintype "bidirectional"))
      (node (ref "D7") (pin "1") (pinfunction "P$1_1") (pintype "bidirectional"))
      (node (ref "D8") (pin "10") (pinfunction "GND_10") (pintype "passive"))
      (node (ref "D9") (pin "1") (pinfunction "P$1_1") (pintype "bidirectional"))
      (node (ref "NGFF1") (pin "11") (pinfunction "GND_11") (pintype "power_in"))
      (node (ref "NGFF1") (pin "27") (pinfunction "GND_27") (pintype "power_in"))
      (node (ref "NGFF1") (pin "3") (pinfunction "GND_3") (pintype "power_in"))
      (node (ref "NGFF1") (pin "33") (pinfunction "GND_33") (pintype "power_in"))
      (node (ref "NGFF1") (pin "39") (pinfunction "GND_39") (pintype "power_in"))
      (node (ref "NGFF1") (pin "45") (pinfunction "GND_45") (pintype "power_in"))
      (node (ref "NGFF1") (pin "5") (pinfunction "GND_5") (pintype "power_in"))
      (node (ref "NGFF1") (pin "51") (pinfunction "GND_51") (pintype "power_in"))
      (node (ref "NGFF1") (pin "57") (pinfunction "GND_57") (pintype "power_in"))
      (node (ref "NGFF1") (pin "71") (pinfunction "GND_71") (pintype "power_in"))
      (node (ref "NGFF1") (pin "73") (pinfunction "GND_73") (pintype "power_in"))
      (node (ref "NGFF1") (pin "P$1") (pinfunction "GND_P$1") (pintype "power_in"))
      (node (ref "NGFF1") (pin "P$2") (pinfunction "GND_P$2") (pintype "power_in"))
      (node (ref "R12") (pin "1") (pinfunction "1_1") (pintype "passive"))
      (node (ref "R21") (pin "1") (pinfunction "1_1") (pintype "passive"))
      (node (ref "R22") (pin "1") (pinfunction "1_1") (pintype "passive"))
      (node (ref "R23") (pin "1") (pinfunction "1_1") (pintype "passive"))
      (node (ref "R8") (pin "1") (pinfunction "1_1") (pintype "passive"))
      (node (ref "R9") (pin "1") (pinfunction "1_1") (pintype "passive"))
      (node (ref "SIM1") (pin "5") (pinfunction "GND_5") (pintype "power_in"))
      (node (ref "SIM2") (pin "5") (pinfunction "GND_5") (pintype "power_in"))
      (node (ref "U1") (pin "2") (pinfunction "GND_2") (pintype "power_in"))
      (node (ref "U2") (pin "2") (pinfunction "GND_2") (pintype "power_in"))
      (node (ref "U2") (pin "4") (pinfunction "GND_4") (pintype "power_in"))
      (node (ref "X1") (pin "4") (pinfunction "4_4") (pintype "passive"))
      (node (ref "X1") (pin "6") (pinfunction "6_6") (pintype "passive"))
      (node (ref "X1") (pin "8") (pinfunction "8_8") (pintype "passive"))
      (node (ref "X10") (pin "5") (pinfunction "GND_5") (pintype "passive"))
      (node (ref "X10") (pin "8") (pinfunction "GND_8") (pintype "passive"))
      (node (ref "X11") (pin "G1") (pinfunction "GND_G1") (pintype "power_in"))
      (node (ref "X11") (pin "G2") (pinfunction "GND_G2") (pintype "power_in"))
      (node (ref "X11") (pin "G3") (pinfunction "GND_G3") (pintype "power_in"))
      (node (ref "X11") (pin "G4") (pinfunction "GND_G4") (pintype "power_in"))
      (node (ref "X2") (pin "7") (pinfunction "GND_DRAIN_7") (pintype "bidirectional"))
      (node (ref "X3") (pin "2") (pinfunction "2_2") (pintype "passive"))
      (node (ref "X5") (pin "2") (pinfunction "2_2") (pintype "passive"))
      (node (ref "X5") (pin "3") (pinfunction "3_3") (pintype "passive"))
      (node (ref "X7") (pin "G1") (pinfunction "GND_G1") (pintype "power_in"))
      (node (ref "X7") (pin "G2") (pinfunction "GND_G2") (pintype "power_in"))
      (node (ref "X7") (pin "G3") (pinfunction "GND_G3") (pintype "power_in"))
      (node (ref "X7") (pin "G4") (pinfunction "GND_G4") (pintype "power_in"))
      (node (ref "X8") (pin "G1") (pinfunction "GND_G1") (pintype "power_in"))
      (node (ref "X8") (pin "G2") (pinfunction "GND_G2") (pintype "power_in"))
      (node (ref "X8") (pin "G3") (pinfunction "GND_G3") (pintype "power_in"))
      (node (ref "X8") (pin "G4") (pinfunction "GND_G4") (pintype "power_in"))
      (node (ref "X9") (pin "G1") (pinfunction "GND_G1") (pintype "power_in"))
      (node (ref "X9") (pin "G2") (pinfunction "GND_G2") (pintype "power_in"))
      (node (ref "X9") (pin "G3") (pinfunction "GND_G3") (pintype "power_in"))
      (node (ref "X9") (pin "G4") (pinfunction "GND_G4") (pintype "power_in"))
      (node (ref "Y1") (pin "P$1") (pinfunction "GND_P$1") (pintype "power_in"))
      (node (ref "Y1") (pin "P$2") (pinfunction "GND_P$2") (pintype "power_in"))
      (node (ref "Y1") (pin "P$4") (pinfunction "GND_P$4") (pintype "power_in"))
      (node (ref "Y2") (pin "P$1") (pinfunction "GND_P$1") (pintype "power_in"))
      (node (ref "Y2") (pin "P$2") (pinfunction "GND_P$2") (pintype "power_in"))
      (node (ref "Y2") (pin "P$4") (pinfunction "GND_P$4") (pintype "power_in"))
      (node (ref "Y3") (pin "P$1") (pinfunction "GND_P$1") (pintype "power_in"))
      (node (ref "Y3") (pin "P$2") (pinfunction "GND_P$2") (pintype "power_in"))
      (node (ref "Y3") (pin "P$4") (pinfunction "GND_P$4") (pintype "power_in"))
      (node (ref "Y4") (pin "P$1") (pinfunction "GND_P$1") (pintype "power_in"))
      (node (ref "Y4") (pin "P$2") (pinfunction "GND_P$2") (pintype "power_in"))
      (node (ref "Y4") (pin "P$4") (pinfunction "GND_P$4") (pintype "power_in"))
    )
    (net (code "21") (name "Net-(C5-Pad2)") (class "Default")
      (node (ref "C5") (pin "2") (pinfunction "2_2") (pintype "passive"))
      (node (ref "R8") (pin "2") (pinfunction "2_2") (pintype "passive"))
      (node (ref "X2") (pin "SHELL") (pinfunction "SHIELD_SHELL") (pintype "bidirectional"))
      (node (ref "X2") (pin "SHELL1") (pinfunction "SHIELD_SHELL1") (pintype "bidirectional"))
    )
    (net (code "22") (name "Net-(C21-Pad2)") (class "Default")
      (node (ref "C21") (pin "2") (pinfunction "2_2") (pintype "passive"))
      (node (ref "R22") (pin "2") (pinfunction "2_2") (pintype "passive"))
      (node (ref "X10") (pin "S1") (pinfunction "S1_S1") (pintype "passive"))
      (node (ref "X10") (pin "S2") (pinfunction "S1_S2") (pintype "passive"))
      (node (ref "X10") (pin "S3") (pinfunction "S1_S3") (pintype "passive"))
      (node (ref "X10") (pin "S4") (pinfunction "S1_S4") (pintype "passive"))
      (node (ref "X10") (pin "S5") (pinfunction "S1_S5") (pintype "passive"))
      (node (ref "X10") (pin "S6") (pinfunction "S1_S6") (pintype "passive"))
      (node (ref "X10") (pin "S7") (pinfunction "S1_S7") (pintype "passive"))
      (node (ref "X10") (pin "S8") (pinfunction "S1_S8") (pintype "passive"))
    )
    (net (code "23") (name "Net-(D2-PadA)") (class "Default")
      (node (ref "D2") (pin "A") (pinfunction "A_A") (pintype "passive"))
      (node (ref "X5") (pin "1") (pinfunction "1_1") (pintype "passive"))
      (node (ref "X5") (pin "1-1") (pinfunction "1_1-1") (pintype "passive"))
    )
    (net (code "24") (name "Net-(D2-PadC)") (class "Default")
      (node (ref "D2") (pin "C") (pinfunction "C_C") (pintype "passive"))
      (node (ref "D3") (pin "C") (pinfunction "C_C") (pintype "passive"))
      (node (ref "X6") (pin "3") (pinfunction "3_3") (pintype "passive"))
    )
    (net (code "25") (name "Net-(D5-P$2)") (class "Default")
      (node (ref "D5") (pin "2") (pinfunction "P$2_2") (pintype "bidirectional"))
      (node (ref "X7") (pin "C") (pinfunction "1_C") (pintype "passive"))
      (node (ref "Y1") (pin "1") (pinfunction "1_1") (pintype "passive"))
    )
    (net (code "26") (name "Net-(D6-P$2)") (class "Default")
      (node (ref "D6") (pin "2") (pinfunction "P$2_2") (pintype "bidirectional"))
      (node (ref "X8") (pin "C") (pinfunction "1_C") (pintype "passive"))
      (node (ref "Y2") (pin "1") (pinfunction "1_1") (pintype "passive"))
    )
    (net (code "27") (name "Net-(D7-P$2)") (class "Default")
      (node (ref "D7") (pin "2") (pinfunction "P$2_2") (pintype "bidirectional"))
      (node (ref "X9") (pin "C") (pinfunction "1_C") (pintype "passive"))
      (node (ref "Y3") (pin "1") (pinfunction "1_1") (pintype "passive"))
    )
    (net (code "28") (name "Net-(D9-P$2)") (class "Default")
      (node (ref "D9") (pin "2") (pinfunction "P$2_2") (pintype "bidirectional"))
      (node (ref "X11") (pin "C") (pinfunction "1_C") (pintype "passive"))
      (node (ref "Y4") (pin "1") (pinfunction "1_1") (pintype "passive"))
    )
    (net (code "29") (name "Net-(LED1-PadC)") (class "Default")
      (node (ref "LED1") (pin "C") (pinfunction "C_C") (pintype "passive"))
      (node (ref "R2") (pin "1") (pinfunction "1_1") (pintype "passive"))
    )
    (net (code "30") (name "Net-(LED2-PadC)") (class "Default")
      (node (ref "LED2") (pin "C") (pinfunction "C_C") (pintype "passive"))
      (node (ref "R23") (pin "2") (pinfunction "2_2") (pintype "passive"))
    )
    (net (code "31") (name "Net-(NGFF1A-~{LED})") (class "Default")
      (node (ref "NGFF1") (pin "10") (pinfunction "~{LED}_10") (pintype "output"))
      (node (ref "R2") (pin "2") (pinfunction "2_2") (pintype "passive"))
    )
    (net (code "32") (name "Net-(R3-Pad1)") (class "Default")
      (node (ref "R3") (pin "1") (pinfunction "1_1") (pintype "passive"))
      (node (ref "X1") (pin "2") (pinfunction "2_2") (pintype "passive"))
    )
    (net (code "33") (name "Net-(R17-Pad1)") (class "Default")
      (node (ref "R17") (pin "1") (pinfunction "1_1") (pintype "passive"))
      (node (ref "X4") (pin "6") (pinfunction "6_6") (pintype "passive"))
    )
    (net (code "34") (name "Net-(R18-Pad1)") (class "Default")
      (node (ref "R18") (pin "1") (pinfunction "1_1") (pintype "passive"))
      (node (ref "X4") (pin "8") (pinfunction "8_8") (pintype "passive"))
    )
    (net (code "35") (name "Net-(R19-Pad1)") (class "Default")
      (node (ref "R19") (pin "1") (pinfunction "1_1") (pintype "passive"))
      (node (ref "X4") (pin "10") (pinfunction "10_10") (pintype "passive"))
    )
    (net (code "36") (name "Net-(SIM1B-1)") (class "Default")
      (node (ref "R11") (pin "2") (pinfunction "2_2") (pintype "passive"))
      (node (ref "SIM1") (pin "82") (pinfunction "1_82") (pintype "passive"))
    )
    (net (code "37") (name "Net-(SIM2B-1)") (class "Default")
      (node (ref "R20") (pin "2") (pinfunction "2_2") (pintype "passive"))
      (node (ref "SIM2") (pin "82") (pinfunction "1_82") (pintype "passive"))
    )
    (net (code "38") (name "Net-(U2-IN)") (class "Default")
      (node (ref "C11") (pin "+") (pinfunction "+_+") (pintype "passive"))
      (node (ref "C13") (pin "2") (pinfunction "2_2") (pintype "passive"))
      (node (ref "U2") (pin "1") (pinfunction "IN_1") (pintype "input"))
      (node (ref "X6") (pin "2") (pinfunction "2_2") (pintype "passive"))
    )
    (net (code "39") (name "PCIE_RX_N") (class "Default")
      (node (ref "NGFF1") (pin "47") (pinfunction "PCIE_RX_N_47") (pintype "input"))
      (node (ref "X2") (pin "8") (pinfunction "STDA_SSTX-_8") (pintype "bidirectional"))
    )
    (net (code "40") (name "PCIE_RX_P") (class "Default")
      (node (ref "NGFF1") (pin "49") (pinfunction "PCIE_RX_P_49") (pintype "input"))
      (node (ref "X2") (pin "9") (pinfunction "STDA_SSTX+_9") (pintype "bidirectional"))
    )
    (net (code "41") (name "PCIE_TX_N") (class "Default")
      (node (ref "NGFF1") (pin "41") (pinfunction "PCIE_TX_N_41") (pintype "output"))
      (node (ref "X2") (pin "5") (pinfunction "STDA_SSRX-_5") (pintype "bidirectional"))
    )
    (net (code "42") (name "PCIE_TX_P") (class "Default")
      (node (ref "NGFF1") (pin "43") (pinfunction "PCIE_TX_P_43") (pintype "output"))
      (node (ref "X2") (pin "6") (pinfunction "STDA_SSRX+_6") (pintype "bidirectional"))
    )
    (net (code "43") (name "PCM_CLK") (class "Default")
      (node (ref "NGFF1") (pin "20") (pinfunction "PCM_CLK/I2S_CLK_20") (pintype "bidirectional"))
      (node (ref "X3") (pin "5") (pinfunction "5_5") (pintype "passive"))
    )
    (net (code "44") (name "PCM_DIN") (class "Default")
      (node (ref "NGFF1") (pin "22") (pinfunction "PCM_DIN/I2S_DIN_22") (pintype "input"))
      (node (ref "X3") (pin "3") (pinfunction "3_3") (pintype "passive"))
    )
    (net (code "45") (name "PCM_DOUT") (class "Default")
      (node (ref "NGFF1") (pin "24") (pinfunction "PCM_DOUT/I2S_DOUT_24") (pintype "output"))
      (node (ref "X3") (pin "7") (pinfunction "7_7") (pintype "passive"))
    )
    (net (code "46") (name "PCM_SYNC") (class "Default")
      (node (ref "NGFF1") (pin "28") (pinfunction "PCM_SYNC/I2S_WS_28") (pintype "bidirectional"))
      (node (ref "X3") (pin "8") (pinfunction "8_8") (pintype "passive"))
    )
    (net (code "47") (name "PWR_ON") (class "Default")
      (node (ref "NGFF1") (pin "6") (pinfunction "PWR_ON_OFF_6") (pintype "input"))
      (node (ref "R9") (pin "2") (pinfunction "2_2") (pintype "passive"))
      (node (ref "X1") (pin "1") (pinfunction "1_1") (pintype "passive"))
    )
    (net (code "48") (name "REFCLK_N") (class "Default")
      (node (ref "NGFF1") (pin "53") (pinfunction "PCIE_REFCLK_N_53") (pintype "input"))
      (node (ref "X2") (pin "2") (pinfunction "D-_2") (pintype "bidirectional"))
    )
    (net (code "49") (name "REFCLK_P") (class "Default")
      (node (ref "NGFF1") (pin "55") (pinfunction "PCIE_REFCLK_P_55") (pintype "input"))
      (node (ref "X2") (pin "3") (pinfunction "D+_3") (pintype "bidirectional"))
    )
    (net (code "50") (name "SIM1_DET") (class "Default")
      (node (ref "NGFF1") (pin "66") (pinfunction "SIM_DET_66") (pintype "input"))
      (node (ref "R12") (pin "2") (pinfunction "2_2") (pintype "passive"))
      (node (ref "SIM1") (pin "81") (pinfunction "0_81") (pintype "passive"))
    )
    (net (code "51") (name "SIM2_DET") (class "Default")
      (node (ref "R21") (pin "2") (pinfunction "2_2") (pintype "passive"))
      (node (ref "SIM2") (pin "81") (pinfunction "0_81") (pintype "passive"))
      (node (ref "X4") (pin "4") (pinfunction "4_4") (pintype "passive"))
    )
    (net (code "52") (name "SMB_CLK") (class "Default")
      (node (ref "NGFF1") (pin "58") (pinfunction "I2C_SCL_SIWI_58") (pintype "output"))
      (node (ref "X3") (pin "11") (pinfunction "11_11") (pintype "passive"))
    )
    (net (code "53") (name "SMB_DATA") (class "Default")
      (node (ref "NGFF1") (pin "56") (pinfunction "I2C_SDA_SIWI_56") (pintype "bidirectional"))
      (node (ref "X3") (pin "12") (pinfunction "12_12") (pintype "passive"))
    )
    (net (code "54") (name "USB3.0_RX_N") (class "Default")
      (node (ref "D8") (pin "9") (pinfunction "7_9") (pintype "passive"))
      (node (ref "NGFF1") (pin "35") (pinfunction "USB3.0_RX_N_35") (pintype "passive"))
      (node (ref "X10") (pin "9") (pinfunction "RX-_9") (pintype "passive"))
    )
    (net (code "55") (name "USB3.0_RX_P") (class "Default")
      (node (ref "D8") (pin "8") (pinfunction "6_8") (pintype "passive"))
      (node (ref "NGFF1") (pin "37") (pinfunction "USB3.0_RX_P_37") (pintype "passive"))
      (node (ref "X10") (pin "10") (pinfunction "RX+_10") (pintype "passive"))
    )
    (net (code "56") (name "USB3.0_TX_N") (class "Default")
      (node (ref "D8") (pin "12") (pinfunction "2_12") (pintype "passive"))
      (node (ref "NGFF1") (pin "29") (pinfunction "USB3.0_TX_N_29") (pintype "passive"))
      (node (ref "X10") (pin "6") (pinfunction "TX-_6") (pintype "passive"))
    )
    (net (code "57") (name "USB3.0_TX_P") (class "Default")
      (node (ref "D8") (pin "11") (pinfunction "1_11") (pintype "passive"))
      (node (ref "NGFF1") (pin "31") (pinfunction "USB3.0_TX_P_31") (pintype "passive"))
      (node (ref "X10") (pin "7") (pinfunction "TX+_7") (pintype "passive"))
    )
    (net (code "58") (name "USB_VBUS") (class "Default")
      (node (ref "X10") (pin "1") (pinfunction "VBUS_1") (pintype "passive"))
      (node (ref "X6") (pin "1") (pinfunction "1_1") (pintype "passive"))
    )
    (net (code "59") (name "USIM1_CLK") (class "Default")
      (node (ref "C3") (pin "1") (pinfunction "1_1") (pintype "passive"))
      (node (ref "R14") (pin "2") (pinfunction "2_2") (pintype "passive"))
      (node (ref "SIM1") (pin "3") (pinfunction "CLK_3") (pintype "input"))
    )
    (net (code "60") (name "USIM1_DATA") (class "Default")
      (node (ref "C4") (pin "1") (pinfunction "1_1") (pintype "passive"))
      (node (ref "R1") (pin "2") (pinfunction "2_2") (pintype "passive"))
      (node (ref "R16") (pin "2") (pinfunction "2_2") (pintype "passive"))
      (node (ref "SIM1") (pin "7") (pinfunction "I/O_7") (pintype "bidirectional"))
    )
    (net (code "61") (name "USIM1_POWER") (class "Default")
      (node (ref "C1") (pin "2") (pinfunction "2_2") (pintype "passive"))
      (node (ref "D1") (pin "5") (pinfunction "5_5") (pintype "passive"))
      (node (ref "NGFF1") (pin "36") (pinfunction "UIM_PWR_36") (pintype "power_in"))
      (node (ref "R1") (pin "1") (pinfunction "1_1") (pintype "passive"))
      (node (ref "SIM1") (pin "1") (pinfunction "VCC_1") (pintype "power_in"))
    )
    (net (code "62") (name "USIM2_CLK") (class "Default")
      (node (ref "C8") (pin "1") (pinfunction "1_1") (pintype "passive"))
      (node (ref "D4") (pin "3") (pinfunction "3_3") (pintype "passive"))
      (node (ref "R19") (pin "2") (pinfunction "2_2") (pintype "passive"))
      (node (ref "SIM2") (pin "3") (pinfunction "CLK_3") (pintype "input"))
    )
    (net (code "63") (name "USIM2_DATA") (class "Default")
      (node (ref "C9") (pin "1") (pinfunction "1_1") (pintype "passive"))
      (node (ref "D4") (pin "6") (pinfunction "6_6") (pintype "passive"))
      (node (ref "R13") (pin "2") (pinfunction "2_2") (pintype "passive"))
      (node (ref "R17") (pin "2") (pinfunction "2_2") (pintype "passive"))
      (node (ref "SIM2") (pin "7") (pinfunction "I/O_7") (pintype "bidirectional"))
    )
    (net (code "64") (name "USIM2_POWER") (class "Default")
      (node (ref "C6") (pin "2") (pinfunction "2_2") (pintype "passive"))
      (node (ref "D4") (pin "5") (pinfunction "5_5") (pintype "passive"))
      (node (ref "R13") (pin "1") (pinfunction "1_1") (pintype "passive"))
      (node (ref "SIM2") (pin "1") (pinfunction "VCC_1") (pintype "power_in"))
      (node (ref "X4") (pin "2") (pinfunction "2_2") (pintype "passive"))
    )
    (net (code "65") (name "VCC_1V8") (class "Default")
      (node (ref "C12") (pin "2") (pinfunction "2_2") (pintype "passive"))
      (node (ref "R10") (pin "2") (pinfunction "2_2") (pintype "passive"))
      (node (ref "R11") (pin "1") (pinfunction "1_1") (pintype "passive"))
      (node (ref "R20") (pin "1") (pinfunction "1_1") (pintype "passive"))
      (node (ref "R3") (pin "2") (pinfunction "2_2") (pintype "passive"))
      (node (ref "R4") (pin "2") (pinfunction "2_2") (pintype "passive"))
      (node (ref "R5") (pin "2") (pinfunction "2_2") (pintype "passive"))
      (node (ref "R6") (pin "2") (pinfunction "2_2") (pintype "passive"))
      (node (ref "R7") (pin "2") (pinfunction "2_2") (pintype "passive"))
      (node (ref "U1") (pin "5") (pinfunction "OUT_5") (pintype "passive"))
      (node (ref "X3") (pin "19") (pinfunction "19_19") (pintype "passive"))
    )
    (net (code "66") (name "VCC_3V3") (class "Default")
      (node (ref "C10") (pin "2") (pinfunction "2_2") (pintype "passive"))
      (node (ref "C14") (pin "2") (pinfunction "2_2") (pintype "passive"))
      (node (ref "C15") (pin "+") (pinfunction "+_+") (pintype "passive"))
      (node (ref "C16") (pin "2") (pinfunction "2_2") (pintype "passive"))
      (node (ref "C17") (pin "2") (pinfunction "2_2") (pintype "passive"))
      (node (ref "C18") (pin "2") (pinfunction "2_2") (pintype "passive"))
      (node (ref "C19") (pin "1") (pinfunction "1_1") (pintype "passive"))
      (node (ref "C20") (pin "1") (pinfunction "1_1") (pintype "passive"))
      (node (ref "C22") (pin "2") (pinfunction "2_2") (pintype "passive"))
      (node (ref "C23") (pin "2") (pinfunction "2_2") (pintype "passive"))
      (node (ref "C24") (pin "2") (pinfunction "2_2") (pintype "passive"))
      (node (ref "C25") (pin "1") (pinfunction "1_1") (pintype "passive"))
      (node (ref "C26") (pin "1") (pinfunction "1_1") (pintype "passive"))
      (node (ref "LED1") (pin "A") (pinfunction "A_A") (pintype "passive"))
      (node (ref "LED2") (pin "A") (pinfunction "A_A") (pintype "passive"))
      (node (ref "NGFF1") (pin "2") (pinfunction "3.3V_2") (pintype "power_in"))
      (node (ref "NGFF1") (pin "4") (pinfunction "3.3V_4") (pintype "power_in"))
      (node (ref "NGFF1") (pin "70") (pinfunction "3.3V_70") (pintype "power_in"))
      (node (ref "NGFF1") (pin "72") (pinfunction "3.3V_72") (pintype "power_in"))
      (node (ref "NGFF1") (pin "74") (pinfunction "3.3V_74") (pintype "power_in"))
      (node (ref "U1") (pin "1") (pinfunction "IN_1") (pintype "input"))
      (node (ref "U1") (pin "3") (pinfunction "EN_3") (pintype "input"))
      (node (ref "U2") (pin "3") (pinfunction "OUT_3") (pintype "passive"))
      (node (ref "X3") (pin "1") (pinfunction "1_1") (pintype "passive"))
    )
    (net (code "67") (name "_SIM2_DET") (class "Default")
      (node (ref "NGFF1") (pin "40") (pinfunction "I2C_SCL_HW/SIM_DET2_SIWI_40") (pintype "output"))
      (node (ref "X4") (pin "3") (pinfunction "3_3") (pintype "passive"))
    )
    (net (code "68") (name "_USB_D_N") (class "Default")
      (node (ref "D8") (pin "14") (pinfunction "5_14") (pintype "passive"))
      (node (ref "NGFF1") (pin "9") (pinfunction "USB_D_N_9") (pintype "passive"))
      (node (ref "X10") (pin "2") (pinfunction "D-_2") (pintype "passive"))
    )
    (net (code "69") (name "_USB_D_P") (class "Default")
      (node (ref "D8") (pin "13") (pinfunction "4_13") (pintype "passive"))
      (node (ref "NGFF1") (pin "7") (pinfunction "USB_D_P_7") (pintype "passive"))
      (node (ref "X10") (pin "3") (pinfunction "D+_3") (pintype "passive"))
    )
    (net (code "70") (name "_USIM1_CLK") (class "Default")
      (node (ref "D1") (pin "1") (pinfunction "1_1") (pintype "passive"))
      (node (ref "NGFF1") (pin "32") (pinfunction "UIM_CLK_32") (pintype "output"))
      (node (ref "R14") (pin "1") (pinfunction "1_1") (pintype "passive"))
    )
    (net (code "71") (name "_USIM1_DATA") (class "Default")
      (node (ref "D1") (pin "4") (pinfunction "4_4") (pintype "passive"))
      (node (ref "NGFF1") (pin "34") (pinfunction "UIM_DATA_34") (pintype "bidirectional"))
      (node (ref "R16") (pin "1") (pinfunction "1_1") (pintype "passive"))
    )
    (net (code "72") (name "_USIM2_CLK") (class "Default")
      (node (ref "NGFF1") (pin "44") (pinfunction "I2C_IRQ_HW/UIM2_CLK_SIWI_44") (pintype "input"))
      (node (ref "X4") (pin "9") (pinfunction "9_9") (pintype "passive"))
    )
    (net (code "73") (name "_USIM2_DATA") (class "Default")
      (node (ref "NGFF1") (pin "42") (pinfunction "I2C_SDA_HW/UIM2_DATA_SIWI_42") (pintype "bidirectional"))
      (node (ref "X4") (pin "5") (pinfunction "5_5") (pintype "passive"))
    )
    (net (code "74") (name "_USIM2_POWER") (class "Default")
      (node (ref "NGFF1") (pin "48") (pinfunction "TX_BLANKING_HW/UIM2_PWR_SIWI_48") (pintype "output"))
      (node (ref "X4") (pin "1") (pinfunction "1_1") (pintype "passive"))
    )
    (net (code "75") (name "unconnected-(D1-Pad3)") (class "Default")
      (node (ref "D1") (pin "3") (pinfunction "3_3") (pintype "passive"))
    )
    (net (code "76") (name "unconnected-(D4-Pad4)") (class "Default")
      (node (ref "D4") (pin "4") (pinfunction "4_4") (pintype "passive"))
    )
    (net (code "77") (name "unconnected-(NGFF1A-CONFIG_0-Pad21)") (class "Default")
      (node (ref "NGFF1") (pin "21") (pinfunction "CONFIG_0_21") (pintype "bidirectional"))
    )
    (net (code "78") (name "unconnected-(NGFF1A-CONFIG_1-Pad69)") (class "Default")
      (node (ref "NGFF1") (pin "69") (pinfunction "CONFIG_1_69") (pintype "output"))
    )
    (net (code "79") (name "unconnected-(NGFF1A-CONFIG_2-Pad75)") (class "Default")
      (node (ref "NGFF1") (pin "75") (pinfunction "CONFIG_2_75") (pintype "output"))
    )
    (net (code "80") (name "unconnected-(NGFF1A-CONFIG_3-Pad1)") (class "Default")
      (node (ref "NGFF1") (pin "1") (pinfunction "CONFIG_3_1") (pintype "bidirectional"))
    )
    (net (code "81") (name "unconnected-(SIM1A-VPP-Pad6)") (class "Default")
      (node (ref "SIM1") (pin "6") (pinfunction "VPP_6") (pintype "power_in"))
    )
    (net (code "82") (name "unconnected-(SIM2A-VPP-Pad6)") (class "Default")
      (node (ref "SIM2") (pin "6") (pinfunction "VPP_6") (pintype "power_in"))
    )
    (net (code "83") (name "unconnected-(X10-ID-Pad4)") (class "Default")
      (node (ref "X10") (pin "4") (pinfunction "ID_4") (pintype "passive"))
    )
  )
)
